# MoWeSta-Weatherstation.net
KiCad netlist of a schematic drawn in EAGLE
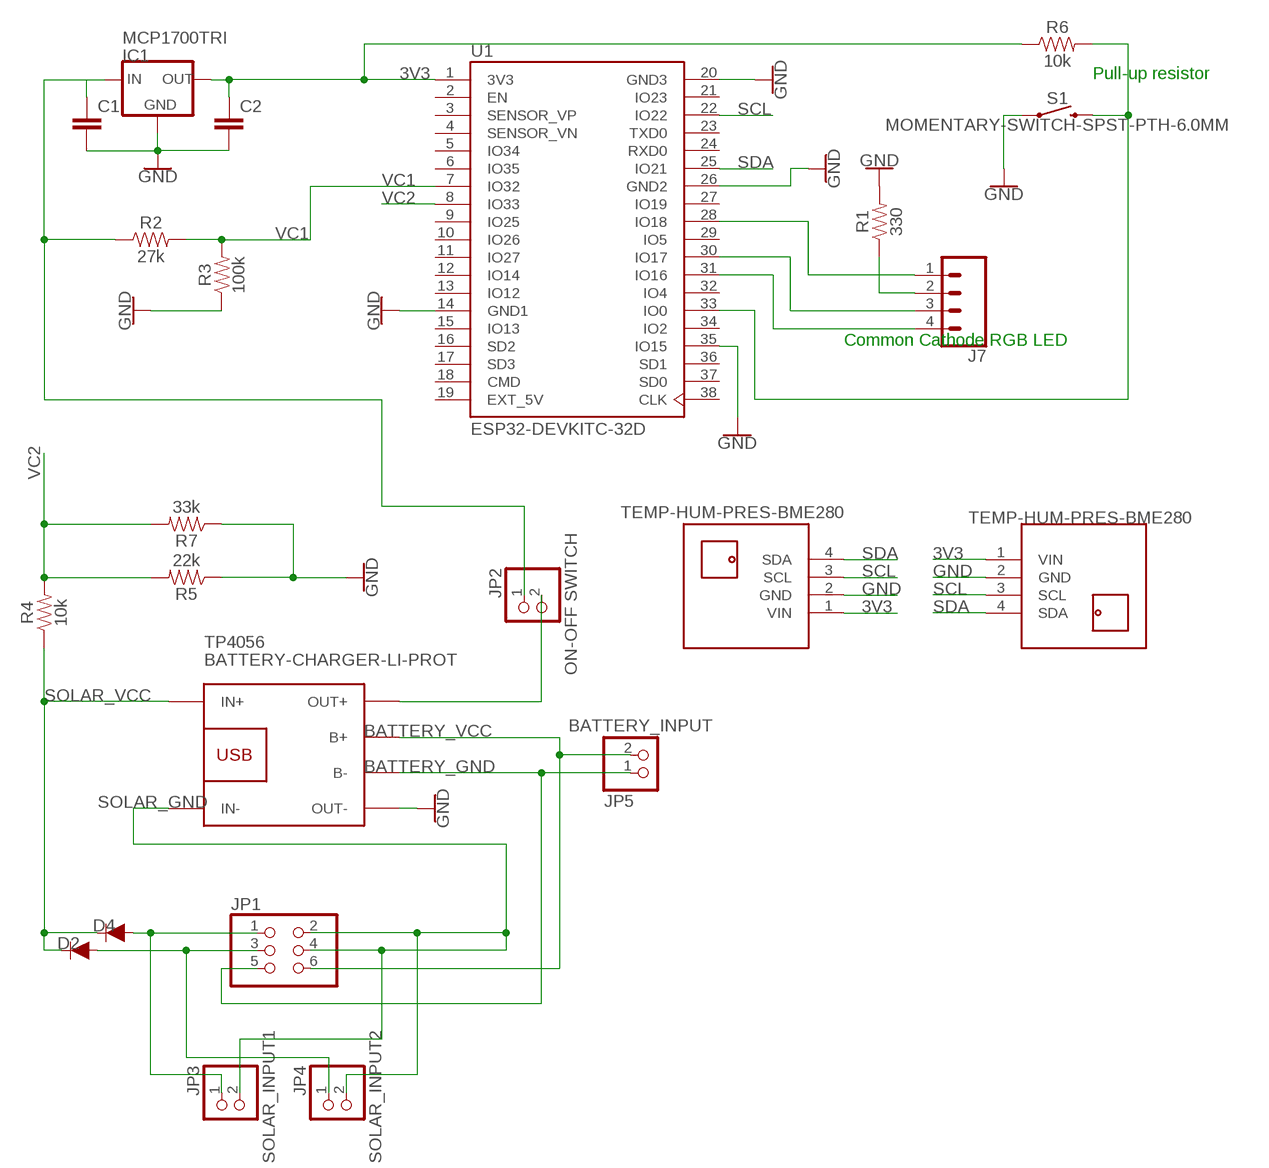
[diagram p0: schematic, sheet 1]

(export (version "E")
  (design (tool "Eeschema 10.0.6"))
  (components
    (comp (ref "C1")
      (value "10nF")
      (footprint "eagle-import:C050-025X075")
      (libsource (lib "eagle-import") (part "C-EU050-025X075"))
    )
    (comp (ref "C2")
      (value "C-EU050-025X075")
      (footprint "eagle-import:C050-025X075")
      (libsource (lib "eagle-import") (part "C-EU050-025X075"))
    )
    (comp (ref "D2")
      (value "1A/50V/1.1V")
      (footprint "eagle-import:DIODE-1N4001")
      (libsource (lib "eagle-import") (part "DIODE-PTH"))
    )
    (comp (ref "D4")
      (value "1A/50V/1.1V")
      (footprint "eagle-import:DIODE-1N4001")
      (libsource (lib "eagle-import") (part "DIODE-PTH"))
    )
    (comp (ref "IC1")
      (value "MCP1700TRI")
      (footprint "eagle-import:TO92-INLINE")
      (libsource (lib "eagle-import") (part "MCP1700INLINE"))
    )
    (comp (ref "J7")
      (value "CONN_04")
      (footprint "eagle-import:1X04")
      (libsource (lib "eagle-import") (part "CONN_04"))
    )
    (comp (ref "JP1")
      (value "PINHD-2X3/90")
      (footprint "eagle-import:2X03_90")
      (libsource (lib "eagle-import") (part "PINHD-2X3/90"))
    )
    (comp (ref "JP2")
      (value "ON-OFF SWITCH")
      (footprint "eagle-import:1X02")
      (libsource (lib "eagle-import") (part "PINHD-1X2"))
    )
    (comp (ref "JP3")
      (value "SOLAR_INPUT1")
      (footprint "eagle-import:1X02")
      (libsource (lib "eagle-import") (part "PINHD-1X2"))
    )
    (comp (ref "JP4")
      (value "SOLAR_INPUT2")
      (footprint "eagle-import:1X02")
      (libsource (lib "eagle-import") (part "PINHD-1X2"))
    )
    (comp (ref "JP5")
      (value "BATTERY_INPUT")
      (footprint "eagle-import:1X02")
      (libsource (lib "eagle-import") (part "PINHD-1X2"))
    )
    (comp (ref "R1")
      (value "330")
      (footprint "eagle-import:AXIAL-0.3")
      (libsource (lib "eagle-import") (part "1KOHM-HORIZ-1/4W-1%"))
    )
    (comp (ref "R2")
      (value "27k")
      (footprint "eagle-import:AXIAL-0.3")
      (libsource (lib "eagle-import") (part "1KOHM-HORIZ-1/4W-1%"))
    )
    (comp (ref "R3")
      (value "100k")
      (footprint "eagle-import:AXIAL-0.3")
      (libsource (lib "eagle-import") (part "1KOHM-HORIZ-1/4W-1%"))
    )
    (comp (ref "R4")
      (value "10k")
      (footprint "eagle-import:AXIAL-0.3")
      (libsource (lib "eagle-import") (part "1KOHM-HORIZ-1/4W-1%"))
    )
    (comp (ref "R5")
      (value "22k")
      (footprint "eagle-import:AXIAL-0.3")
      (libsource (lib "eagle-import") (part "1KOHM-HORIZ-1/4W-1%"))
    )
    (comp (ref "R6")
      (value "10k")
      (footprint "eagle-import:AXIAL-0.3")
      (libsource (lib "eagle-import") (part "1KOHM-HORIZ-1/4W-1%"))
    )
    (comp (ref "R7")
      (value "33k")
      (footprint "eagle-import:AXIAL-0.3")
      (libsource (lib "eagle-import") (part "1KOHM-HORIZ-1/4W-1%"))
    )
    (comp (ref "S1")
      (value "MOMENTARY-SWITCH-SPST-PTH-6.0MM")
      (footprint "eagle-import:TACTILE_SWITCH_PTH_6.0MM")
      (libsource (lib "eagle-import") (part "MOMENTARY-SWITCH-SPST-PTH-6.0MM"))
    )
    (comp (ref "TP4056")
      (value "BATTERY-CHARGER-LI-PROT")
      (footprint "eagle-import:BATTERY-CHARGER-LI-PROT")
      (libsource (lib "eagle-import") (part "BATTERY-CHARGER-LI-PROT"))
    )
    (comp (ref "U$3")
      (value "TEMP-HUM-PRES-BME280")
      (footprint "eagle-import:TEMP-HUM-PRES-BME280")
      (libsource (lib "eagle-import") (part "TEMP-HUM-PRES-BME280"))
    )
    (comp (ref "U$4")
      (value "TEMP-HUM-PRES-BME280")
      (footprint "eagle-import:TEMP-HUM-PRES-BME280")
      (libsource (lib "eagle-import") (part "TEMP-HUM-PRES-BME280"))
    )
    (comp (ref "U1")
      (value "ESP32-DEVKITC-32D")
      (footprint "eagle-import:MODULE_ESP32-DEVKITC-32D")
      (fields (field (name "MF") "Espressif Systems"))
      (libsource (lib "eagle-import") (part "ESP32-DEVKITC-32D"))
    )
  )
  (nets
    (net (code "1") (name "/3V3") (class "Default")
      (node (ref "C2") (pin "1") (pinfunction "1_1") (pintype "passive"))
      (node (ref "IC1") (pin "3") (pinfunction "OUT_3") (pintype "passive"))
      (node (ref "R6") (pin "P$1") (pinfunction "1_P$1") (pintype "passive"))
      (node (ref "U$3") (pin "1") (pinfunction "VIN_1") (pintype "power_in"))
      (node (ref "U$4") (pin "1") (pinfunction "VIN_1") (pintype "power_in"))
      (node (ref "U1") (pin "1") (pinfunction "3V3_1") (pintype "power_in"))
    )
    (net (code "2") (name "/BATTERY_GND") (class "Default")
      (node (ref "JP1") (pin "5") (pinfunction "5_5") (pintype "passive"))
      (node (ref "JP5") (pin "1") (pinfunction "1_1") (pintype "passive"))
      (node (ref "TP4056") (pin "B-") (pinfunction "B-_B-") (pintype "bidirectional"))
    )
    (net (code "3") (name "/BATTERY_VCC") (class "Default")
      (node (ref "JP1") (pin "6") (pinfunction "6_6") (pintype "passive"))
      (node (ref "JP5") (pin "2") (pinfunction "2_2") (pintype "passive"))
      (node (ref "TP4056") (pin "B+") (pinfunction "B+_B+") (pintype "bidirectional"))
    )
    (net (code "4") (name "/EXT_5V") (class "Default")
      (node (ref "U1") (pin "19") (pinfunction "EXT_5V_19") (pintype "power_in"))
    )
    (net (code "5") (name "/SCL") (class "Default")
      (node (ref "U$3") (pin "3") (pinfunction "SCL_3") (pintype "bidirectional"))
      (node (ref "U$4") (pin "3") (pinfunction "SCL_3") (pintype "bidirectional"))
      (node (ref "U1") (pin "22") (pinfunction "IO22_22") (pintype "bidirectional"))
    )
    (net (code "6") (name "/SDA") (class "Default")
      (node (ref "U$3") (pin "4") (pinfunction "SDA_4") (pintype "bidirectional"))
      (node (ref "U$4") (pin "4") (pinfunction "SDA_4") (pintype "bidirectional"))
      (node (ref "U1") (pin "25") (pinfunction "IO21_25") (pintype "bidirectional"))
    )
    (net (code "7") (name "/SOLAR_GND") (class "Default")
      (node (ref "JP1") (pin "2") (pinfunction "2_2") (pintype "passive"))
      (node (ref "JP1") (pin "4") (pinfunction "4_4") (pintype "passive"))
      (node (ref "JP3") (pin "2") (pinfunction "2_2") (pintype "passive"))
      (node (ref "JP4") (pin "2") (pinfunction "2_2") (pintype "passive"))
      (node (ref "TP4056") (pin "IN-") (pinfunction "IN-_IN-") (pintype "bidirectional"))
    )
    (net (code "8") (name "/SOLAR_VCC") (class "Default")
      (node (ref "D2") (pin "C") (pinfunction "C_C") (pintype "passive"))
      (node (ref "D4") (pin "C") (pinfunction "C_C") (pintype "passive"))
      (node (ref "R4") (pin "P$1") (pinfunction "1_P$1") (pintype "passive"))
      (node (ref "TP4056") (pin "IN+") (pinfunction "IN+_IN+") (pintype "bidirectional"))
    )
    (net (code "9") (name "/VC1") (class "Default")
      (node (ref "R2") (pin "P$2") (pinfunction "2_P$2") (pintype "passive"))
      (node (ref "R3") (pin "P$2") (pinfunction "2_P$2") (pintype "passive"))
      (node (ref "U1") (pin "7") (pinfunction "IO32_7") (pintype "bidirectional"))
    )
    (net (code "10") (name "/VC2") (class "Default")
      (node (ref "R4") (pin "P$2") (pinfunction "2_P$2") (pintype "passive"))
      (node (ref "R5") (pin "P$2") (pinfunction "2_P$2") (pintype "passive"))
      (node (ref "R7") (pin "P$2") (pinfunction "2_P$2") (pintype "passive"))
      (node (ref "U1") (pin "8") (pinfunction "IO33_8") (pintype "bidirectional"))
    )
    (net (code "11") (name "GND") (class "Default")
      (node (ref "C1") (pin "2") (pinfunction "2_2") (pintype "passive"))
      (node (ref "C2") (pin "2") (pinfunction "2_2") (pintype "passive"))
      (node (ref "IC1") (pin "1") (pinfunction "GND_1") (pintype "input"))
      (node (ref "R1") (pin "P$2") (pinfunction "2_P$2") (pintype "passive"))
      (node (ref "R3") (pin "P$1") (pinfunction "1_P$1") (pintype "passive"))
      (node (ref "R5") (pin "P$1") (pinfunction "1_P$1") (pintype "passive"))
      (node (ref "R7") (pin "P$1") (pinfunction "1_P$1") (pintype "passive"))
      (node (ref "S1") (pin "1") (pinfunction "1_1") (pintype "passive"))
      (node (ref "TP4056") (pin "OUT-") (pinfunction "OUT-_OUT-") (pintype "bidirectional"))
      (node (ref "U$3") (pin "2") (pinfunction "GND_2") (pintype "power_in"))
      (node (ref "U$4") (pin "2") (pinfunction "GND_2") (pintype "power_in"))
      (node (ref "U1") (pin "14") (pinfunction "GND1_14") (pintype "power_in"))
      (node (ref "U1") (pin "20") (pinfunction "GND3_20") (pintype "power_in"))
      (node (ref "U1") (pin "26") (pinfunction "GND2_26") (pintype "power_in"))
      (node (ref "U1") (pin "35") (pinfunction "IO15_35") (pintype "bidirectional"))
    )
    (net (code "12") (name "Net-(D2-PadA)") (class "Default")
      (node (ref "D2") (pin "A") (pinfunction "A_A") (pintype "passive"))
      (node (ref "JP1") (pin "3") (pinfunction "3_3") (pintype "passive"))
      (node (ref "JP4") (pin "1") (pinfunction "1_1") (pintype "passive"))
    )
    (net (code "13") (name "Net-(D4-PadA)") (class "Default")
      (node (ref "D4") (pin "A") (pinfunction "A_A") (pintype "passive"))
      (node (ref "JP1") (pin "1") (pinfunction "1_1") (pintype "passive"))
      (node (ref "JP3") (pin "1") (pinfunction "1_1") (pintype "passive"))
    )
    (net (code "14") (name "Net-(IC1-IN)") (class "Default")
      (node (ref "C1") (pin "1") (pinfunction "1_1") (pintype "passive"))
      (node (ref "IC1") (pin "2") (pinfunction "IN_2") (pintype "input"))
      (node (ref "JP2") (pin "1") (pinfunction "1_1") (pintype "passive"))
      (node (ref "R2") (pin "P$1") (pinfunction "1_P$1") (pintype "passive"))
    )
    (net (code "15") (name "Net-(JP2-Pad2)") (class "Default")
      (node (ref "JP2") (pin "2") (pinfunction "2_2") (pintype "passive"))
      (node (ref "TP4056") (pin "OUT+") (pinfunction "OUT+_OUT+") (pintype "bidirectional"))
    )
    (net (code "16") (name "Net-(R1-1)") (class "Default")
      (node (ref "J7") (pin "2") (pinfunction "2_2") (pintype "passive"))
      (node (ref "R1") (pin "P$1") (pinfunction "1_P$1") (pintype "passive"))
    )
    (net (code "17") (name "Net-(R6-2)") (class "Default")
      (node (ref "R6") (pin "P$2") (pinfunction "2_P$2") (pintype "passive"))
      (node (ref "S1") (pin "3") (pinfunction "2_3") (pintype "passive"))
      (node (ref "U1") (pin "33") (pinfunction "IO0_33") (pintype "bidirectional"))
    )
    (net (code "18") (name "Net-(U1-IO16)") (class "Default")
      (node (ref "J7") (pin "4") (pinfunction "4_4") (pintype "passive"))
      (node (ref "U1") (pin "31") (pinfunction "IO16_31") (pintype "bidirectional"))
    )
    (net (code "19") (name "Net-(U1-IO17)") (class "Default")
      (node (ref "J7") (pin "3") (pinfunction "3_3") (pintype "passive"))
      (node (ref "U1") (pin "30") (pinfunction "IO17_30") (pintype "bidirectional"))
    )
    (net (code "20") (name "Net-(U1-IO18)") (class "Default")
      (node (ref "J7") (pin "1") (pinfunction "1_1") (pintype "passive"))
      (node (ref "U1") (pin "28") (pinfunction "IO18_28") (pintype "bidirectional"))
    )
    (net (code "21") (name "unconnected-(U1-CLK-Pad38)") (class "Default")
      (node (ref "U1") (pin "38") (pinfunction "CLK_38") (pintype "input"))
    )
    (net (code "22") (name "unconnected-(U1-CMD-Pad18)") (class "Default")
      (node (ref "U1") (pin "18") (pinfunction "CMD_18") (pintype "bidirectional"))
    )
    (net (code "23") (name "unconnected-(U1-EN-Pad2)") (class "Default")
      (node (ref "U1") (pin "2") (pinfunction "EN_2") (pintype "input"))
    )
    (net (code "24") (name "unconnected-(U1-IO2-Pad34)") (class "Default")
      (node (ref "U1") (pin "34") (pinfunction "IO2_34") (pintype "bidirectional"))
    )
    (net (code "25") (name "unconnected-(U1-IO4-Pad32)") (class "Default")
      (node (ref "U1") (pin "32") (pinfunction "IO4_32") (pintype "bidirectional"))
    )
    (net (code "26") (name "unconnected-(U1-IO5-Pad29)") (class "Default")
      (node (ref "U1") (pin "29") (pinfunction "IO5_29") (pintype "bidirectional"))
    )
    (net (code "27") (name "unconnected-(U1-IO12-Pad13)") (class "Default")
      (node (ref "U1") (pin "13") (pinfunction "IO12_13") (pintype "bidirectional"))
    )
    (net (code "28") (name "unconnected-(U1-IO13-Pad15)") (class "Default")
      (node (ref "U1") (pin "15") (pinfunction "IO13_15") (pintype "bidirectional"))
    )
    (net (code "29") (name "unconnected-(U1-IO14-Pad12)") (class "Default")
      (node (ref "U1") (pin "12") (pinfunction "IO14_12") (pintype "bidirectional"))
    )
    (net (code "30") (name "unconnected-(U1-IO19-Pad27)") (class "Default")
      (node (ref "U1") (pin "27") (pinfunction "IO19_27") (pintype "bidirectional"))
    )
    (net (code "31") (name "unconnected-(U1-IO23-Pad21)") (class "Default")
      (node (ref "U1") (pin "21") (pinfunction "IO23_21") (pintype "bidirectional"))
    )
    (net (code "32") (name "unconnected-(U1-IO25-Pad9)") (class "Default")
      (node (ref "U1") (pin "9") (pinfunction "IO25_9") (pintype "bidirectional"))
    )
    (net (code "33") (name "unconnected-(U1-IO26-Pad10)") (class "Default")
      (node (ref "U1") (pin "10") (pinfunction "IO26_10") (pintype "bidirectional"))
    )
    (net (code "34") (name "unconnected-(U1-IO27-Pad11)") (class "Default")
      (node (ref "U1") (pin "11") (pinfunction "IO27_11") (pintype "bidirectional"))
    )
    (net (code "35") (name "unconnected-(U1-IO34-Pad5)") (class "Default")
      (node (ref "U1") (pin "5") (pinfunction "IO34_5") (pintype "bidirectional"))
    )
    (net (code "36") (name "unconnected-(U1-IO35-Pad6)") (class "Default")
      (node (ref "U1") (pin "6") (pinfunction "IO35_6") (pintype "bidirectional"))
    )
    (net (code "37") (name "unconnected-(U1-RXD0-Pad24)") (class "Default")
      (node (ref "U1") (pin "24") (pinfunction "RXD0_24") (pintype "input"))
    )
    (net (code "38") (name "unconnected-(U1-SD0-Pad37)") (class "Default")
      (node (ref "U1") (pin "37") (pinfunction "SD0_37") (pintype "bidirectional"))
    )
    (net (code "39") (name "unconnected-(U1-SD1-Pad36)") (class "Default")
      (node (ref "U1") (pin "36") (pinfunction "SD1_36") (pintype "bidirectional"))
    )
    (net (code "40") (name "unconnected-(U1-SD2-Pad16)") (class "Default")
      (node (ref "U1") (pin "16") (pinfunction "SD2_16") (pintype "bidirectional"))
    )
    (net (code "41") (name "unconnected-(U1-SD3-Pad17)") (class "Default")
      (node (ref "U1") (pin "17") (pinfunction "SD3_17") (pintype "bidirectional"))
    )
    (net (code "42") (name "unconnected-(U1-SENSOR_VN-Pad4)") (class "Default")
      (node (ref "U1") (pin "4") (pinfunction "SENSOR_VN_4") (pintype "input"))
    )
    (net (code "43") (name "unconnected-(U1-SENSOR_VP-Pad3)") (class "Default")
      (node (ref "U1") (pin "3") (pinfunction "SENSOR_VP_3") (pintype "input"))
    )
    (net (code "44") (name "unconnected-(U1-TXD0-Pad23)") (class "Default")
      (node (ref "U1") (pin "23") (pinfunction "TXD0_23") (pintype "output"))
    )
  )
)
